# UD3B.net
KiCad netlist of a schematic drawn in Altium Designer
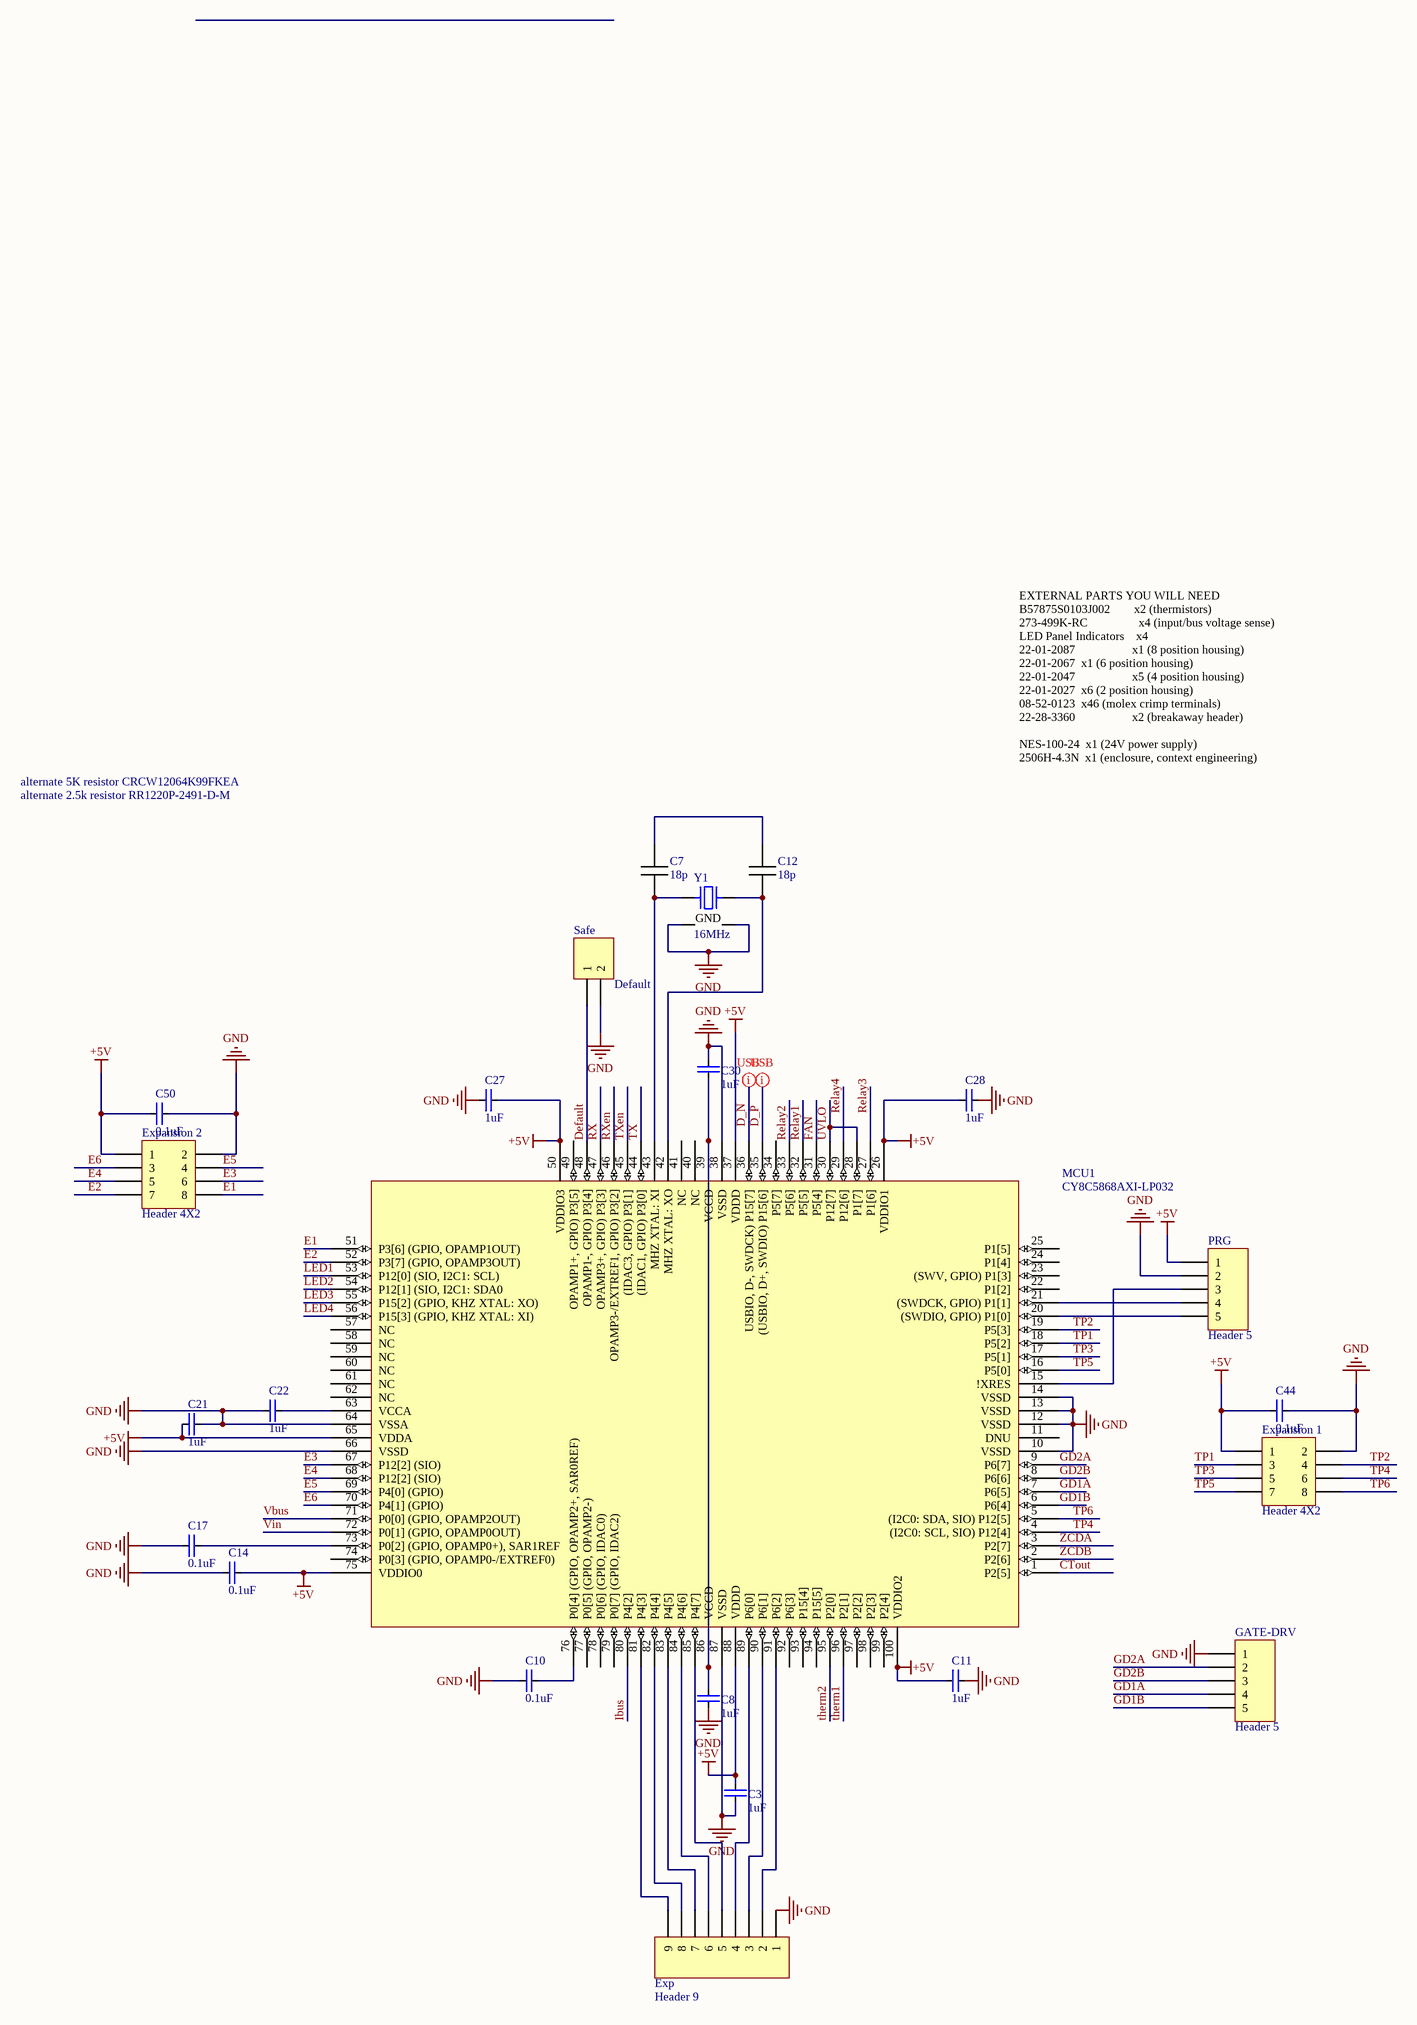
[diagram p0: UD3B.SchDoc]

(export (version "E")
  (design (tool "Eeschema 10.0.6"))
  (components
    (comp (ref "C3")
      (value "1uF")
      (footprint "0805C")
      (description "Capacitor, 1uF, MLCC, 16V, X7R, 10%, SMD")
      (fields (field (name "Comment") "C0805C105K4RACTU"))
      (libsource (lib "steve lib") (part "C0805C105K4RACTU"))
    )
    (comp (ref "C7")
      (value "VJ0805A180GXACW1BC")
      (footprint "0805C")
      (fields (field (name "CAPACITANCE") "18p"))
      (libsource (lib "steve lib") (part "Capacitor"))
    )
    (comp (ref "C8")
      (value "1uF")
      (footprint "0805C")
      (description "Capacitor, 1uF, MLCC, 16V, X7R, 10%, SMD")
      (fields (field (name "Comment") "C0805C105K4RACTU"))
      (libsource (lib "steve lib") (part "C0805C105K4RACTU"))
    )
    (comp (ref "C10")
      (value "0.1uF")
      (footprint "0805C")
      (description "Capacitor, 0.1uF, MLCC, 50V, X7R, 10%, SMD")
      (fields (field (name "Comment") "C0805C104K5RACTU"))
      (libsource (lib "steve lib") (part "C0805C104K5RACTU"))
    )
    (comp (ref "C11")
      (value "1uF")
      (footprint "0805C")
      (description "Capacitor, 1uF, MLCC, 16V, X7R, 10%, SMD")
      (fields (field (name "Comment") "C0805C105K4RACTU"))
      (libsource (lib "steve lib") (part "C0805C105K4RACTU"))
    )
    (comp (ref "C12")
      (value "VJ0805A180GXACW1BC")
      (footprint "0805C")
      (fields (field (name "CAPACITANCE") "18p"))
      (libsource (lib "steve lib") (part "Capacitor"))
    )
    (comp (ref "C14")
      (value "0.1uF")
      (footprint "0805C")
      (description "Capacitor, 0.1uF, MLCC, 50V, X7R, 10%, SMD")
      (fields (field (name "Comment") "C0805C104K5RACTU"))
      (libsource (lib "steve lib") (part "C0805C104K5RACTU"))
    )
    (comp (ref "C17")
      (value "0.1uF")
      (footprint "0805C")
      (description "Capacitor, 0.1uF, MLCC, 50V, X7R, 10%, SMD")
      (fields (field (name "Comment") "C0805C104K5RACTU"))
      (libsource (lib "steve lib") (part "C0805C104K5RACTU"))
    )
    (comp (ref "C21")
      (value "1uF")
      (footprint "0805C")
      (description "Capacitor, 1uF, MLCC, 16V, X7R, 10%, SMD")
      (fields (field (name "Comment") "C0805C105K4RACTU"))
      (libsource (lib "steve lib") (part "C0805C105K4RACTU"))
    )
    (comp (ref "C22")
      (value "1uF")
      (footprint "0805C")
      (description "Capacitor, 1uF, MLCC, 16V, X7R, 10%, SMD")
      (fields (field (name "Comment") "C0805C105K4RACTU"))
      (libsource (lib "steve lib") (part "C0805C105K4RACTU"))
    )
    (comp (ref "C27")
      (value "1uF")
      (footprint "0805C")
      (description "Capacitor, 1uF, MLCC, 16V, X7R, 10%, SMD")
      (fields (field (name "Comment") "C0805C105K4RACTU"))
      (libsource (lib "steve lib") (part "C0805C105K4RACTU"))
    )
    (comp (ref "C28")
      (value "1uF")
      (footprint "0805C")
      (description "Capacitor, 1uF, MLCC, 16V, X7R, 10%, SMD")
      (fields (field (name "Comment") "C0805C105K4RACTU"))
      (libsource (lib "steve lib") (part "C0805C105K4RACTU"))
    )
    (comp (ref "C30")
      (value "1uF")
      (footprint "0805C")
      (description "Capacitor, 1uF, MLCC, 16V, X7R, 10%, SMD")
      (fields (field (name "Comment") "C0805C105K4RACTU"))
      (libsource (lib "steve lib") (part "C0805C105K4RACTU"))
    )
    (comp (ref "C44")
      (value "0.1uF")
      (footprint "0805C")
      (description "Capacitor, 0.1uF, MLCC, 50V, X7R, 10%, SMD")
      (fields (field (name "Comment") "C0805C104K5RACTU"))
      (libsource (lib "Bart_schematic_symbols") (part "C0805C104K5RACTU"))
    )
    (comp (ref "C50")
      (value "0.1uF")
      (footprint "0805C")
      (description "Capacitor, 0.1uF, MLCC, 50V, X7R, 10%, SMD")
      (fields (field (name "Comment") "C0805C104K5RACTU"))
      (libsource (lib "Bart_schematic_symbols") (part "C0805C104K5RACTU"))
    )
    (comp (ref "Exp")
      (value "Header 9")
      (footprint "HDR1X9")
      (description "Header, 9-Pin")
      (fields (field (name "PUBLISHER") "Altium Limited"))
      (libsource (lib "Miscellaneous Connectors") (part "Header 9"))
    )
    (comp (ref "Expansion 1")
      (value "Header 4X2")
      (footprint "HDR2X4")
      (description "Header, 4-Pin, Dual row")
      (fields (field (name "PUBLISHER") "Altium Limited"))
      (libsource (lib "Miscellaneous Connectors") (part "Header 4X2"))
    )
    (comp (ref "Expansion 2")
      (value "Header 4X2")
      (footprint "HDR2X4")
      (description "Header, 4-Pin, Dual row")
      (fields (field (name "PUBLISHER") "Altium Limited"))
      (libsource (lib "Miscellaneous Connectors") (part "Header 4X2"))
    )
    (comp (ref "GATE-DRV")
      (value "Header 5")
      (footprint "HDR1X5")
      (description "Header, 5-Pin")
      (fields (field (name "PUBLISHER") "Altium Limited"))
      (libsource (lib "Miscellaneous Connectors") (part "Header 5"))
    )
    (comp (ref "MCU1")
      (value "CY8C5868AXI-LP032")
      (footprint "TQFP100")
      (libsource (lib "steve lib") (part "CY8C5466AXI-064"))
    )
    (comp (ref "PRG")
      (value "Header 5")
      (footprint "HDR1X5")
      (description "Header, 5-Pin")
      (fields (field (name "PUBLISHER") "Altium Limited"))
      (libsource (lib "Miscellaneous Connectors") (part "Header 5"))
    )
    (comp (ref "Safe")
      (value "Default")
      (footprint "HDR1X2")
      (description "Header, 2-Pin")
      (fields (field (name "PUBLISHER") "Altium Limited"))
      (libsource (lib "Miscellaneous Connectors") (part "Header 2"))
    )
    (comp (ref "Y1")
      (value "16MHz")
      (footprint "ABRACON ABM8G")
      (description "CRYSTAL 16.0000MHZ 18PF SMD")
      (fields
        (field (name "PART NUMBER") "ABM8G-16.000MHZ-18-D2Y-T3")
        (field (name "MANUFACTURER") "Abracon LLC")
      )
      (libsource (lib "Celestial") (part "Abracon Crystal ABM8G"))
    )
  )
  (nets
    (net (code "1") (name "+5V") (class "Default")
      (node (ref "C11") (pin "1") (pinfunction "1_1") (pintype "passive"))
      (node (ref "C14") (pin "2") (pinfunction "2_2") (pintype "passive"))
      (node (ref "C21") (pin "2") (pinfunction "2_2") (pintype "passive"))
      (node (ref "C27") (pin "1") (pinfunction "1_1") (pintype "passive"))
      (node (ref "C28") (pin "2") (pinfunction "2_2") (pintype "passive"))
      (node (ref "C3") (pin "1") (pinfunction "1_1") (pintype "passive"))
      (node (ref "C44") (pin "2") (pinfunction "2_2") (pintype "passive"))
      (node (ref "C50") (pin "2") (pinfunction "2_2") (pintype "passive"))
      (node (ref "Expansion 1") (pin "1") (pinfunction "1_1") (pintype "passive"))
      (node (ref "Expansion 2") (pin "1") (pinfunction "1_1") (pintype "passive"))
      (node (ref "MCU1") (pin "100") (pinfunction "VDDIO2_100") (pintype "passive"))
      (node (ref "MCU1") (pin "26") (pinfunction "VDDIO1_26") (pintype "power_in"))
      (node (ref "MCU1") (pin "37") (pinfunction "VDDD_37") (pintype "power_in"))
      (node (ref "MCU1") (pin "50") (pinfunction "VDDIO3_50") (pintype "power_in"))
      (node (ref "MCU1") (pin "65") (pinfunction "VDDA_65") (pintype "power_in"))
      (node (ref "MCU1") (pin "75") (pinfunction "VDDIO0_75") (pintype "power_in"))
      (node (ref "MCU1") (pin "88") (pinfunction "VDDD_88") (pintype "power_in"))
      (node (ref "PRG") (pin "1") (pinfunction "1_1") (pintype "passive"))
    )
    (net (code "2") (name "/CTout") (class "Default")
      (node (ref "MCU1") (pin "1") (pinfunction "P2[5]_1") (pintype "bidirectional"))
    )
    (net (code "3") (name "/D_N") (class "Default")
      (node (ref "MCU1") (pin "36") (pinfunction "USBIO,_D-,_SWDCK)_P15[7]_36") (pintype "bidirectional"))
    )
    (net (code "4") (name "/D_P") (class "Default")
      (node (ref "MCU1") (pin "35") (pinfunction "(USBIO,_D+,_SWDIO)_P15[6]_35") (pintype "bidirectional"))
    )
    (net (code "5") (name "/Default") (class "Default")
      (node (ref "MCU1") (pin "48") (pinfunction "OPAMP1-,_GPIO)_P3[4]_48") (pintype "bidirectional"))
      (node (ref "Safe") (pin "1") (pinfunction "1_1") (pintype "passive"))
    )
    (net (code "6") (name "/E1") (class "Default")
      (node (ref "Expansion 2") (pin "8") (pinfunction "8_8") (pintype "passive"))
      (node (ref "MCU1") (pin "51") (pinfunction "P3[6]_(GPIO,_OPAMP1OUT)_51") (pintype "bidirectional"))
    )
    (net (code "7") (name "/E2") (class "Default")
      (node (ref "Expansion 2") (pin "7") (pinfunction "7_7") (pintype "passive"))
      (node (ref "MCU1") (pin "52") (pinfunction "P3[7]_(GPIO,_OPAMP3OUT)_52") (pintype "bidirectional"))
    )
    (net (code "8") (name "/E3") (class "Default")
      (node (ref "Expansion 2") (pin "6") (pinfunction "6_6") (pintype "passive"))
      (node (ref "MCU1") (pin "67") (pinfunction "P12[2]_(SIO)_67") (pintype "bidirectional"))
    )
    (net (code "9") (name "/E4") (class "Default")
      (node (ref "Expansion 2") (pin "5") (pinfunction "5_5") (pintype "passive"))
      (node (ref "MCU1") (pin "68") (pinfunction "P12[2]_(SIO)_68") (pintype "bidirectional"))
    )
    (net (code "10") (name "/E5") (class "Default")
      (node (ref "Expansion 2") (pin "4") (pinfunction "4_4") (pintype "passive"))
      (node (ref "MCU1") (pin "69") (pinfunction "P4[0]_(GPIO)_69") (pintype "bidirectional"))
    )
    (net (code "11") (name "/E6") (class "Default")
      (node (ref "Expansion 2") (pin "3") (pinfunction "3_3") (pintype "passive"))
      (node (ref "MCU1") (pin "70") (pinfunction "P4[1]_(GPIO)_70") (pintype "bidirectional"))
    )
    (net (code "12") (name "/FAN") (class "Default")
      (node (ref "MCU1") (pin "31") (pinfunction "P5[4]_31") (pintype "bidirectional"))
    )
    (net (code "13") (name "/GD1A") (class "Default")
      (node (ref "GATE-DRV") (pin "4") (pinfunction "4_4") (pintype "passive"))
      (node (ref "MCU1") (pin "7") (pinfunction "P6[5]_7") (pintype "bidirectional"))
    )
    (net (code "14") (name "/GD1B") (class "Default")
      (node (ref "GATE-DRV") (pin "5") (pinfunction "5_5") (pintype "passive"))
      (node (ref "MCU1") (pin "6") (pinfunction "P6[4]_6") (pintype "bidirectional"))
    )
    (net (code "15") (name "/GD2A") (class "Default")
      (node (ref "GATE-DRV") (pin "2") (pinfunction "2_2") (pintype "passive"))
      (node (ref "MCU1") (pin "9") (pinfunction "P6[7]_9") (pintype "bidirectional"))
    )
    (net (code "16") (name "/GD2B") (class "Default")
      (node (ref "GATE-DRV") (pin "3") (pinfunction "3_3") (pintype "passive"))
      (node (ref "MCU1") (pin "8") (pinfunction "P6[6]_8") (pintype "bidirectional"))
    )
    (net (code "17") (name "/Ibus") (class "Default")
      (node (ref "MCU1") (pin "80") (pinfunction "P4[2]_80") (pintype "bidirectional"))
    )
    (net (code "18") (name "/LED1") (class "Default")
      (node (ref "MCU1") (pin "53") (pinfunction "P12[0]_(SIO,_I2C1:_SCL)_53") (pintype "bidirectional"))
    )
    (net (code "19") (name "/LED2") (class "Default")
      (node (ref "MCU1") (pin "54") (pinfunction "P12[1]_(SIO,_I2C1:_SDA0_54") (pintype "bidirectional"))
    )
    (net (code "20") (name "/LED3") (class "Default")
      (node (ref "MCU1") (pin "55") (pinfunction "P15[2]_(GPIO,_KHZ_XTAL:_XO)_55") (pintype "bidirectional"))
    )
    (net (code "21") (name "/LED4") (class "Default")
      (node (ref "MCU1") (pin "56") (pinfunction "P15[3]_(GPIO,_KHZ_XTAL:_XI)_56") (pintype "bidirectional"))
    )
    (net (code "22") (name "/RX") (class "Default")
      (node (ref "MCU1") (pin "47") (pinfunction "OPAMP3+,_GPIO)_P3[3]_47") (pintype "bidirectional"))
    )
    (net (code "23") (name "/RXen") (class "Default")
      (node (ref "MCU1") (pin "46") (pinfunction "OPAMP3-/EXTREF1,_GPIO)_P3[2]_46") (pintype "bidirectional"))
    )
    (net (code "24") (name "/Relay1") (class "Default")
      (node (ref "MCU1") (pin "32") (pinfunction "P5[5]_32") (pintype "bidirectional"))
    )
    (net (code "25") (name "/Relay2") (class "Default")
      (node (ref "MCU1") (pin "33") (pinfunction "P5[6]_33") (pintype "bidirectional"))
    )
    (net (code "26") (name "/Relay3") (class "Default")
      (node (ref "MCU1") (pin "27") (pinfunction "P1[6]_27") (pintype "bidirectional"))
    )
    (net (code "27") (name "/Relay4") (class "Default")
      (node (ref "MCU1") (pin "29") (pinfunction "P12[6]_29") (pintype "bidirectional"))
    )
    (net (code "28") (name "/TP1") (class "Default")
      (node (ref "Expansion 1") (pin "3") (pinfunction "3_3") (pintype "passive"))
      (node (ref "MCU1") (pin "18") (pinfunction "P5[2]_18") (pintype "bidirectional"))
    )
    (net (code "29") (name "/TP2") (class "Default")
      (node (ref "Expansion 1") (pin "4") (pinfunction "4_4") (pintype "passive"))
      (node (ref "MCU1") (pin "19") (pinfunction "P5[3]_19") (pintype "bidirectional"))
    )
    (net (code "30") (name "/TP3") (class "Default")
      (node (ref "Expansion 1") (pin "5") (pinfunction "5_5") (pintype "passive"))
      (node (ref "MCU1") (pin "17") (pinfunction "P5[1]_17") (pintype "bidirectional"))
    )
    (net (code "31") (name "/TP4") (class "Default")
      (node (ref "Expansion 1") (pin "6") (pinfunction "6_6") (pintype "passive"))
      (node (ref "MCU1") (pin "4") (pinfunction "(I2C0:_SCL,_SIO)_P12[4]_4") (pintype "bidirectional"))
    )
    (net (code "32") (name "/TP5") (class "Default")
      (node (ref "Expansion 1") (pin "7") (pinfunction "7_7") (pintype "passive"))
      (node (ref "MCU1") (pin "16") (pinfunction "P5[0]_16") (pintype "bidirectional"))
    )
    (net (code "33") (name "/TP6") (class "Default")
      (node (ref "Expansion 1") (pin "8") (pinfunction "8_8") (pintype "passive"))
      (node (ref "MCU1") (pin "5") (pinfunction "(I2C0:_SDA,_SIO)_P12[5]_5") (pintype "bidirectional"))
    )
    (net (code "34") (name "/TX") (class "Default")
      (node (ref "MCU1") (pin "44") (pinfunction "(IDAC1,_GPIO)_P3[0]_44") (pintype "bidirectional"))
    )
    (net (code "35") (name "/TXen") (class "Default")
      (node (ref "MCU1") (pin "45") (pinfunction "(IDAC3,_GPIO)_P3[1]_45") (pintype "bidirectional"))
    )
    (net (code "36") (name "/UVLO") (class "Default")
      (node (ref "MCU1") (pin "28") (pinfunction "P1[7]_28") (pintype "bidirectional"))
      (node (ref "MCU1") (pin "30") (pinfunction "P12[7]_30") (pintype "bidirectional"))
    )
    (net (code "37") (name "/Vbus") (class "Default")
      (node (ref "MCU1") (pin "71") (pinfunction "P0[0]_(GPIO,_OPAMP2OUT)_71") (pintype "bidirectional"))
    )
    (net (code "38") (name "/Vin") (class "Default")
      (node (ref "MCU1") (pin "72") (pinfunction "P0[1]_(GPIO,_OPAMP0OUT)_72") (pintype "bidirectional"))
    )
    (net (code "39") (name "/ZCDA") (class "Default")
      (node (ref "MCU1") (pin "3") (pinfunction "P2[7]_3") (pintype "bidirectional"))
    )
    (net (code "40") (name "/ZCDB") (class "Default")
      (node (ref "MCU1") (pin "2") (pinfunction "P2[6]_2") (pintype "bidirectional"))
    )
    (net (code "41") (name "/therm1") (class "Default")
      (node (ref "MCU1") (pin "96") (pinfunction "P2[1]_96") (pintype "bidirectional"))
    )
    (net (code "42") (name "/therm2") (class "Default")
      (node (ref "MCU1") (pin "95") (pinfunction "P2[0]_95") (pintype "bidirectional"))
    )
    (net (code "43") (name "GND") (class "Default")
      (node (ref "C10") (pin "1") (pinfunction "1_1") (pintype "passive"))
      (node (ref "C11") (pin "2") (pinfunction "2_2") (pintype "passive"))
      (node (ref "C14") (pin "1") (pinfunction "1_1") (pintype "passive"))
      (node (ref "C17") (pin "1") (pinfunction "1_1") (pintype "passive"))
      (node (ref "C21") (pin "1") (pinfunction "1_1") (pintype "passive"))
      (node (ref "C22") (pin "2") (pinfunction "2_2") (pintype "passive"))
      (node (ref "C27") (pin "2") (pinfunction "2_2") (pintype "passive"))
      (node (ref "C28") (pin "1") (pinfunction "1_1") (pintype "passive"))
      (node (ref "C3") (pin "2") (pinfunction "2_2") (pintype "passive"))
      (node (ref "C30") (pin "2") (pinfunction "2_2") (pintype "passive"))
      (node (ref "C44") (pin "1") (pinfunction "1_1") (pintype "passive"))
      (node (ref "C50") (pin "1") (pinfunction "1_1") (pintype "passive"))
      (node (ref "C8") (pin "2") (pinfunction "2_2") (pintype "passive"))
      (node (ref "Exp") (pin "1") (pinfunction "1_1") (pintype "passive"))
      (node (ref "Expansion 1") (pin "2") (pinfunction "2_2") (pintype "passive"))
      (node (ref "Expansion 2") (pin "2") (pinfunction "2_2") (pintype "passive"))
      (node (ref "GATE-DRV") (pin "1") (pinfunction "1_1") (pintype "passive"))
      (node (ref "MCU1") (pin "10") (pinfunction "VSSD_10") (pintype "power_in"))
      (node (ref "MCU1") (pin "12") (pinfunction "VSSD_12") (pintype "power_in"))
      (node (ref "MCU1") (pin "13") (pinfunction "VSSD_13") (pintype "power_in"))
      (node (ref "MCU1") (pin "14") (pinfunction "VSSD_14") (pintype "power_in"))
      (node (ref "MCU1") (pin "38") (pinfunction "VSSD_38") (pintype "power_in"))
      (node (ref "MCU1") (pin "64") (pinfunction "VSSA_64") (pintype "power_in"))
      (node (ref "MCU1") (pin "66") (pinfunction "VSSD_66") (pintype "power_in"))
      (node (ref "MCU1") (pin "87") (pinfunction "VSSD_87") (pintype "power_in"))
      (node (ref "PRG") (pin "2") (pinfunction "2_2") (pintype "passive"))
      (node (ref "Safe") (pin "2") (pinfunction "2_2") (pintype "passive"))
      (node (ref "Y1") (pin "2") (pinfunction "GND_2") (pintype "passive"))
      (node (ref "Y1") (pin "4") (pinfunction "GND_4") (pintype "passive"))
    )
    (net (code "44") (name "Net-(C12-Pad1)") (class "Default")
      (node (ref "C12") (pin "1") (pinfunction "1_1") (pintype "passive"))
      (node (ref "C7") (pin "1") (pinfunction "1_1") (pintype "passive"))
    )
    (net (code "45") (name "Net-(C30-Pad1)") (class "Default")
      (node (ref "C30") (pin "1") (pinfunction "1_1") (pintype "passive"))
      (node (ref "C8") (pin "1") (pinfunction "1_1") (pintype "passive"))
      (node (ref "MCU1") (pin "39") (pinfunction "VCCD_39") (pintype "power_in"))
      (node (ref "MCU1") (pin "86") (pinfunction "VCCD_86") (pintype "power_in"))
    )
    (net (code "46") (name "Net-(MCU1-!XRES)") (class "Default")
      (node (ref "MCU1") (pin "15") (pinfunction "!XRES_15") (pintype "passive"))
      (node (ref "PRG") (pin "3") (pinfunction "3_3") (pintype "passive"))
    )
    (net (code "47") (name "Net-(MCU1-(SWDCK,_GPIO)_P1[1])") (class "Default")
      (node (ref "MCU1") (pin "21") (pinfunction "(SWDCK,_GPIO)_P1[1]_21") (pintype "bidirectional"))
      (node (ref "PRG") (pin "4") (pinfunction "4_4") (pintype "passive"))
    )
    (net (code "48") (name "Net-(MCU1-(SWDIO,_GPIO)_P1[0])") (class "Default")
      (node (ref "MCU1") (pin "20") (pinfunction "(SWDIO,_GPIO)_P1[0]_20") (pintype "bidirectional"))
      (node (ref "PRG") (pin "5") (pinfunction "5_5") (pintype "passive"))
    )
    (net (code "49") (name "Net-(MCU1-MHZ_XTAL:_XI)") (class "Default")
      (node (ref "C7") (pin "2") (pinfunction "2_2") (pintype "passive"))
      (node (ref "MCU1") (pin "43") (pinfunction "MHZ_XTAL:_XI_43") (pintype "passive"))
      (node (ref "Y1") (pin "1") (pinfunction "1_1") (pintype "passive"))
    )
    (net (code "50") (name "Net-(MCU1-MHZ_XTAL:_XO)") (class "Default")
      (node (ref "C12") (pin "2") (pinfunction "2_2") (pintype "passive"))
      (node (ref "MCU1") (pin "42") (pinfunction "MHZ_XTAL:_XO_42") (pintype "passive"))
      (node (ref "Y1") (pin "3") (pinfunction "3_3") (pintype "passive"))
    )
    (net (code "51") (name "Net-(MCU1-P0[2]_(GPIO,_OPAMP0+),_SAR1REF)") (class "Default")
      (node (ref "C17") (pin "2") (pinfunction "2_2") (pintype "passive"))
      (node (ref "MCU1") (pin "73") (pinfunction "P0[2]_(GPIO,_OPAMP0+),_SAR1REF_73") (pintype "bidirectional"))
    )
    (net (code "52") (name "Net-(MCU1-P0[4]_(GPIO,_OPAMP2+,_SAR0REF))") (class "Default")
      (node (ref "C10") (pin "2") (pinfunction "2_2") (pintype "passive"))
      (node (ref "MCU1") (pin "76") (pinfunction "P0[4]_(GPIO,_OPAMP2+,_SAR0REF)_76") (pintype "bidirectional"))
    )
    (net (code "53") (name "Net-(MCU1-P4[3])") (class "Default")
      (node (ref "Exp") (pin "9") (pinfunction "9_9") (pintype "passive"))
      (node (ref "MCU1") (pin "81") (pinfunction "P4[3]_81") (pintype "bidirectional"))
    )
    (net (code "54") (name "Net-(MCU1-P4[4])") (class "Default")
      (node (ref "Exp") (pin "8") (pinfunction "8_8") (pintype "passive"))
      (node (ref "MCU1") (pin "82") (pinfunction "P4[4]_82") (pintype "bidirectional"))
    )
    (net (code "55") (name "Net-(MCU1-P4[5])") (class "Default")
      (node (ref "Exp") (pin "7") (pinfunction "7_7") (pintype "passive"))
      (node (ref "MCU1") (pin "83") (pinfunction "P4[5]_83") (pintype "bidirectional"))
    )
    (net (code "56") (name "Net-(MCU1-P4[6])") (class "Default")
      (node (ref "Exp") (pin "6") (pinfunction "6_6") (pintype "passive"))
      (node (ref "MCU1") (pin "84") (pinfunction "P4[6]_84") (pintype "bidirectional"))
    )
    (net (code "57") (name "Net-(MCU1-P4[7])") (class "Default")
      (node (ref "Exp") (pin "5") (pinfunction "5_5") (pintype "passive"))
      (node (ref "MCU1") (pin "85") (pinfunction "P4[7]_85") (pintype "bidirectional"))
    )
    (net (code "58") (name "Net-(MCU1-P6[0])") (class "Default")
      (node (ref "Exp") (pin "4") (pinfunction "4_4") (pintype "passive"))
      (node (ref "MCU1") (pin "89") (pinfunction "P6[0]_89") (pintype "bidirectional"))
    )
    (net (code "59") (name "Net-(MCU1-P6[1])") (class "Default")
      (node (ref "Exp") (pin "3") (pinfunction "3_3") (pintype "passive"))
      (node (ref "MCU1") (pin "90") (pinfunction "P6[1]_90") (pintype "bidirectional"))
    )
    (net (code "60") (name "Net-(MCU1-P6[2])") (class "Default")
      (node (ref "Exp") (pin "2") (pinfunction "2_2") (pintype "passive"))
      (node (ref "MCU1") (pin "91") (pinfunction "P6[2]_91") (pintype "bidirectional"))
    )
    (net (code "61") (name "Net-(MCU1-VCCA)") (class "Default")
      (node (ref "C22") (pin "1") (pinfunction "1_1") (pintype "passive"))
      (node (ref "MCU1") (pin "63") (pinfunction "VCCA_63") (pintype "power_in"))
    )
    (net (code "62") (name "unconnected-(MCU1-(SWV,_GPIO)_P1[3]-Pad23)") (class "Default")
      (node (ref "MCU1") (pin "23") (pinfunction "(SWV,_GPIO)_P1[3]_23") (pintype "bidirectional"))
    )
    (net (code "63") (name "unconnected-(MCU1-DNU-Pad11)") (class "Default")
      (node (ref "MCU1") (pin "11") (pinfunction "DNU_11") (pintype "passive"))
    )
    (net (code "64") (name "unconnected-(MCU1-NC-Pad40)") (class "Default")
      (node (ref "MCU1") (pin "40") (pinfunction "NC_40") (pintype "passive"))
    )
    (net (code "65") (name "unconnected-(MCU1-NC-Pad41)") (class "Default")
      (node (ref "MCU1") (pin "41") (pinfunction "NC_41") (pintype "passive"))
    )
    (net (code "66") (name "unconnected-(MCU1-NC-Pad57)") (class "Default")
      (node (ref "MCU1") (pin "57") (pinfunction "NC_57") (pintype "passive"))
    )
    (net (code "67") (name "unconnected-(MCU1-NC-Pad58)") (class "Default")
      (node (ref "MCU1") (pin "58") (pinfunction "NC_58") (pintype "passive"))
    )
    (net (code "68") (name "unconnected-(MCU1-NC-Pad59)") (class "Default")
      (node (ref "MCU1") (pin "59") (pinfunction "NC_59") (pintype "passive"))
    )
    (net (code "69") (name "unconnected-(MCU1-NC-Pad60)") (class "Default")
      (node (ref "MCU1") (pin "60") (pinfunction "NC_60") (pintype "passive"))
    )
    (net (code "70") (name "unconnected-(MCU1-NC-Pad61)") (class "Default")
      (node (ref "MCU1") (pin "61") (pinfunction "NC_61") (pintype "passive"))
    )
    (net (code "71") (name "unconnected-(MCU1-NC-Pad62)") (class "Default")
      (node (ref "MCU1") (pin "62") (pinfunction "NC_62") (pintype "passive"))
    )
    (net (code "72") (name "unconnected-(MCU1-OPAMP1+,_GPIO)_P3[5]-Pad49)") (class "Default")
      (node (ref "MCU1") (pin "49") (pinfunction "OPAMP1+,_GPIO)_P3[5]_49") (pintype "bidirectional"))
    )
    (net (code "73") (name "unconnected-(MCU1-P0[3]_(GPIO,_OPAMP0-{slash}EXTREF0)-Pad74)") (class "Default")
      (node (ref "MCU1") (pin "74") (pinfunction "P0[3]_(GPIO,_OPAMP0-/EXTREF0)_74") (pintype "bidirectional"))
    )
    (net (code "74") (name "unconnected-(MCU1-P0[5]_(GPIO,_OPAMP2-)-Pad77)") (class "Default")
      (node (ref "MCU1") (pin "77") (pinfunction "P0[5]_(GPIO,_OPAMP2-)_77") (pintype "bidirectional"))
    )
    (net (code "75") (name "unconnected-(MCU1-P0[6]_(GPIO,_IDAC0)-Pad78)") (class "Default")
      (node (ref "MCU1") (pin "78") (pinfunction "P0[6]_(GPIO,_IDAC0)_78") (pintype "bidirectional"))
    )
    (net (code "76") (name "unconnected-(MCU1-P0[7]_(GPIO,_IDAC2)-Pad79)") (class "Default")
      (node (ref "MCU1") (pin "79") (pinfunction "P0[7]_(GPIO,_IDAC2)_79") (pintype "bidirectional"))
    )
    (net (code "77") (name "unconnected-(MCU1-P1[2]-Pad22)") (class "Default")
      (node (ref "MCU1") (pin "22") (pinfunction "P1[2]_22") (pintype "bidirectional"))
    )
    (net (code "78") (name "unconnected-(MCU1-P1[4]-Pad24)") (class "Default")
      (node (ref "MCU1") (pin "24") (pinfunction "P1[4]_24") (pintype "bidirectional"))
    )
    (net (code "79") (name "unconnected-(MCU1-P1[5]-Pad25)") (class "Default")
      (node (ref "MCU1") (pin "25") (pinfunction "P1[5]_25") (pintype "bidirectional"))
    )
    (net (code "80") (name "unconnected-(MCU1-P2[2]-Pad97)") (class "Default")
      (node (ref "MCU1") (pin "97") (pinfunction "P2[2]_97") (pintype "bidirectional"))
    )
    (net (code "81") (name "unconnected-(MCU1-P2[3]-Pad98)") (class "Default")
      (node (ref "MCU1") (pin "98") (pinfunction "P2[3]_98") (pintype "bidirectional"))
    )
    (net (code "82") (name "unconnected-(MCU1-P2[4]-Pad99)") (class "Default")
      (node (ref "MCU1") (pin "99") (pinfunction "P2[4]_99") (pintype "bidirectional"))
    )
    (net (code "83") (name "unconnected-(MCU1-P5[7]-Pad34)") (class "Default")
      (node (ref "MCU1") (pin "34") (pinfunction "P5[7]_34") (pintype "bidirectional"))
    )
    (net (code "84") (name "unconnected-(MCU1-P6[3]-Pad92)") (class "Default")
      (node (ref "MCU1") (pin "92") (pinfunction "P6[3]_92") (pintype "bidirectional"))
    )
    (net (code "85") (name "unconnected-(MCU1-P15[4]-Pad93)") (class "Default")
      (node (ref "MCU1") (pin "93") (pinfunction "P15[4]_93") (pintype "bidirectional"))
    )
    (net (code "86") (name "unconnected-(MCU1-P15[5]-Pad94)") (class "Default")
      (node (ref "MCU1") (pin "94") (pinfunction "P15[5]_94") (pintype "bidirectional"))
    )
  )
)
